# Power.net
KiCad netlist of a schematic drawn in Altium Designer
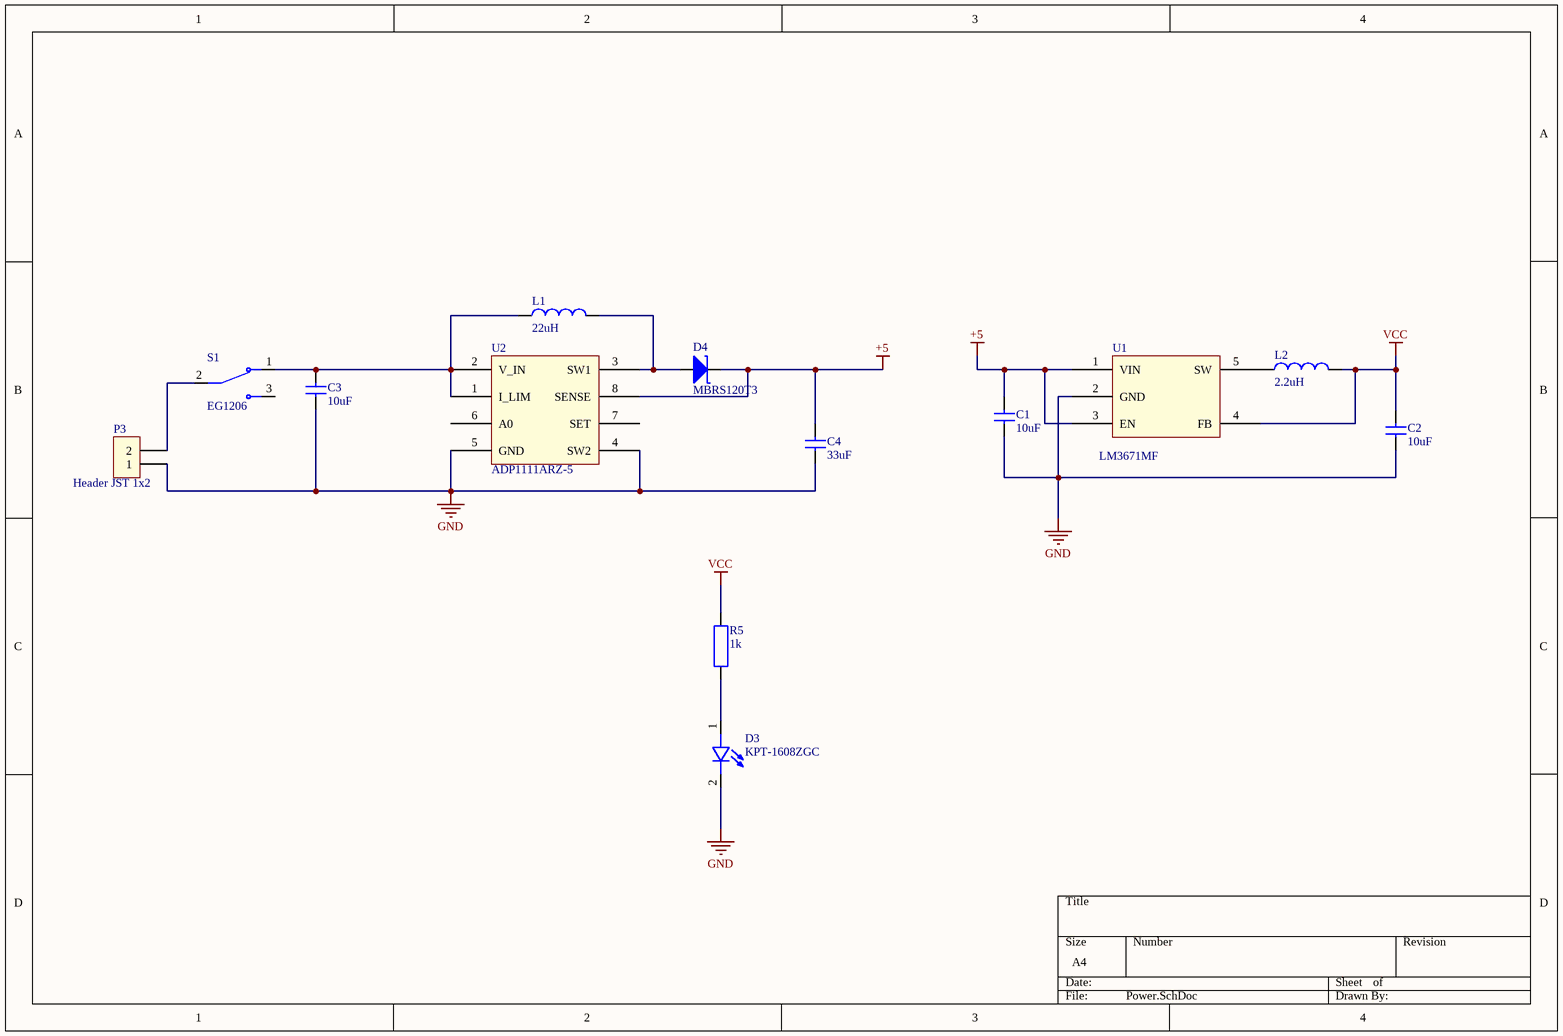
[diagram p0: Power.SchDoc]

(export (version "E")
  (design (tool "Eeschema 10.0.6"))
  (components
    (comp (ref "C1")
      (value "10uF")
      (footprint "SMD_CAPACITOR_1206")
      (description "Capacitor")
      (libsource (lib "VPP_Library") (part "Capacitor"))
    )
    (comp (ref "C2")
      (value "10uF")
      (footprint "SMD_CAPACITOR_1206")
      (description "Capacitor")
      (libsource (lib "VPP_Library") (part "Capacitor"))
    )
    (comp (ref "C3")
      (value "10uF")
      (footprint "SMD_CAPACITOR_1206")
      (description "Capacitor")
      (fields (field (name "Comment") "100nF"))
      (libsource (lib "VPP_Library") (part "Capacitor"))
    )
    (comp (ref "C4")
      (value "33uF")
      (footprint "SMD_CAPACITOR_1206")
      (description "Capacitor")
      (fields (field (name "Comment") "100nF"))
      (libsource (lib "VPP_Library") (part "Capacitor"))
    )
    (comp (ref "D3")
      (value "KPT-1608ZGC")
      (footprint "LED_KPT-1608ZGC")
      (description "1.6x0.8mm Smd Chip Led Lamp")
      (fields (field (name "MF") "Kingbright"))
      (libsource (lib "KPT-1608ZGC") (part "KPT-1608ZGC"))
    )
    (comp (ref "D4")
      (value "MBRS120T3")
      (footprint "SMD_DO-214AC")
      (description "Diode Schottky")
      (libsource (lib "VPP_Library") (part "Diode_Schottky"))
    )
    (comp (ref "L1")
      (value "22uH")
      (footprint "SMD_INDUCTOR_7.3MM")
      (description "Inductor")
      (libsource (lib "VPP_Library") (part "Inductor"))
    )
    (comp (ref "L2")
      (value "2.2uH")
      (footprint "SMD_INDUCTOR_0805")
      (description "Inductor")
      (fields (field (name "Comment") "22uH"))
      (libsource (lib "VPP_Library") (part "Inductor"))
    )
    (comp (ref "P3")
      (value "Header JST 1x2")
      (footprint "THT_HEADER_78MIL_JST_1X2_MALE")
      (libsource (lib "VPP_Library") (part "Header_JST_1x2"))
    )
    (comp (ref "R5")
      (value "1k")
      (footprint "SMD_RESISTOR_1206")
      (description "Resistor")
      (libsource (lib "VPP_Library") (part "Resistor"))
    )
    (comp (ref "S1") (value "EG1206") (footprint "SW_EG1206") (libsource (lib "EG1206") (part "EG1206")))
    (comp (ref "U1")
      (value "LM3671MF")
      (footprint "SMD_SOT-23-5")
      (description "Step Down Switching Regulator, Fixed, 2.7V-5.5V Input, 3.3V and 0.6A Output")
      (libsource (lib "VPP_Library") (part "LM3671MF"))
    )
    (comp (ref "U2")
      (value "ADP1111ARZ-5")
      (footprint "SMD_SOIC-8")
      (description "Buck, Boost Switching Regulator, Fixed, 2V-30V Input, 5V and 1.5A Output")
      (libsource (lib "VPP_Library") (part "ADP1111ARZ-5"))
    )
  )
  (nets
    (net (code "1") (name "+5") (class "Default")
      (node (ref "C1") (pin "2") (pinfunction "2_2") (pintype "passive"))
      (node (ref "C4") (pin "2") (pinfunction "2_2") (pintype "passive"))
      (node (ref "D4") (pin "2") (pinfunction "2_2") (pintype "passive"))
      (node (ref "U1") (pin "1") (pinfunction "VIN_1") (pintype "passive"))
      (node (ref "U1") (pin "3") (pinfunction "EN_3") (pintype "passive"))
      (node (ref "U2") (pin "8") (pinfunction "SENSE_8") (pintype "passive"))
    )
    (net (code "2") (name "GND") (class "Default")
      (node (ref "C1") (pin "1") (pinfunction "1_1") (pintype "passive"))
      (node (ref "C2") (pin "2") (pinfunction "2_2") (pintype "passive"))
      (node (ref "C3") (pin "2") (pinfunction "2_2") (pintype "passive"))
      (node (ref "C4") (pin "1") (pinfunction "1_1") (pintype "passive"))
      (node (ref "D3") (pin "2") (pinfunction "C_2") (pintype "passive"))
      (node (ref "P3") (pin "1") (pinfunction "1_1") (pintype "passive"))
      (node (ref "U1") (pin "2") (pinfunction "GND_2") (pintype "passive"))
      (node (ref "U2") (pin "4") (pinfunction "SW2_4") (pintype "passive"))
      (node (ref "U2") (pin "5") (pinfunction "GND_5") (pintype "passive"))
    )
    (net (code "3") (name "Net-(D3-A)") (class "Default")
      (node (ref "D3") (pin "1") (pinfunction "A_1") (pintype "passive"))
      (node (ref "R5") (pin "2") (pinfunction "2_2") (pintype "passive"))
    )
    (net (code "4") (name "Net-(P3-Pad2)") (class "Default")
      (node (ref "P3") (pin "2") (pinfunction "2_2") (pintype "passive"))
      (node (ref "S1") (pin "2") (pinfunction "2_2") (pintype "passive"))
    )
    (net (code "5") (name "Net-(U1-SW)") (class "Default")
      (node (ref "L2") (pin "1") (pinfunction "1_1") (pintype "passive"))
      (node (ref "U1") (pin "5") (pinfunction "SW_5") (pintype "passive"))
    )
    (net (code "6") (name "Net-(U2-I_LIM)") (class "Default")
      (node (ref "C3") (pin "1") (pinfunction "1_1") (pintype "passive"))
      (node (ref "L1") (pin "1") (pinfunction "1_1") (pintype "passive"))
      (node (ref "S1") (pin "1") (pinfunction "1_1") (pintype "passive"))
      (node (ref "U2") (pin "1") (pinfunction "I_LIM_1") (pintype "passive"))
      (node (ref "U2") (pin "2") (pinfunction "V_IN_2") (pintype "passive"))
    )
    (net (code "7") (name "Net-(U2-SW1)") (class "Default")
      (node (ref "D4") (pin "1") (pinfunction "1_1") (pintype "passive"))
      (node (ref "L1") (pin "2") (pinfunction "2_2") (pintype "passive"))
      (node (ref "U2") (pin "3") (pinfunction "SW1_3") (pintype "passive"))
    )
    (net (code "8") (name "VCC") (class "Default")
      (node (ref "C2") (pin "1") (pinfunction "1_1") (pintype "passive"))
      (node (ref "L2") (pin "2") (pinfunction "2_2") (pintype "passive"))
      (node (ref "R5") (pin "1") (pinfunction "1_1") (pintype "passive"))
      (node (ref "U1") (pin "4") (pinfunction "FB_4") (pintype "passive"))
    )
    (net (code "9") (name "unconnected-(S1-Pad3)") (class "Default")
      (node (ref "S1") (pin "3") (pinfunction "3_3") (pintype "passive"))
    )
    (net (code "10") (name "unconnected-(U2-A0-Pad6)") (class "Default")
      (node (ref "U2") (pin "6") (pinfunction "A0_6") (pintype "passive"))
    )
    (net (code "11") (name "unconnected-(U2-SET-Pad7)") (class "Default")
      (node (ref "U2") (pin "7") (pinfunction "SET_7") (pintype "passive"))
    )
  )
)
